# one_dollar_boad_rev4.net
KiCad netlist of a schematic drawn in EAGLE
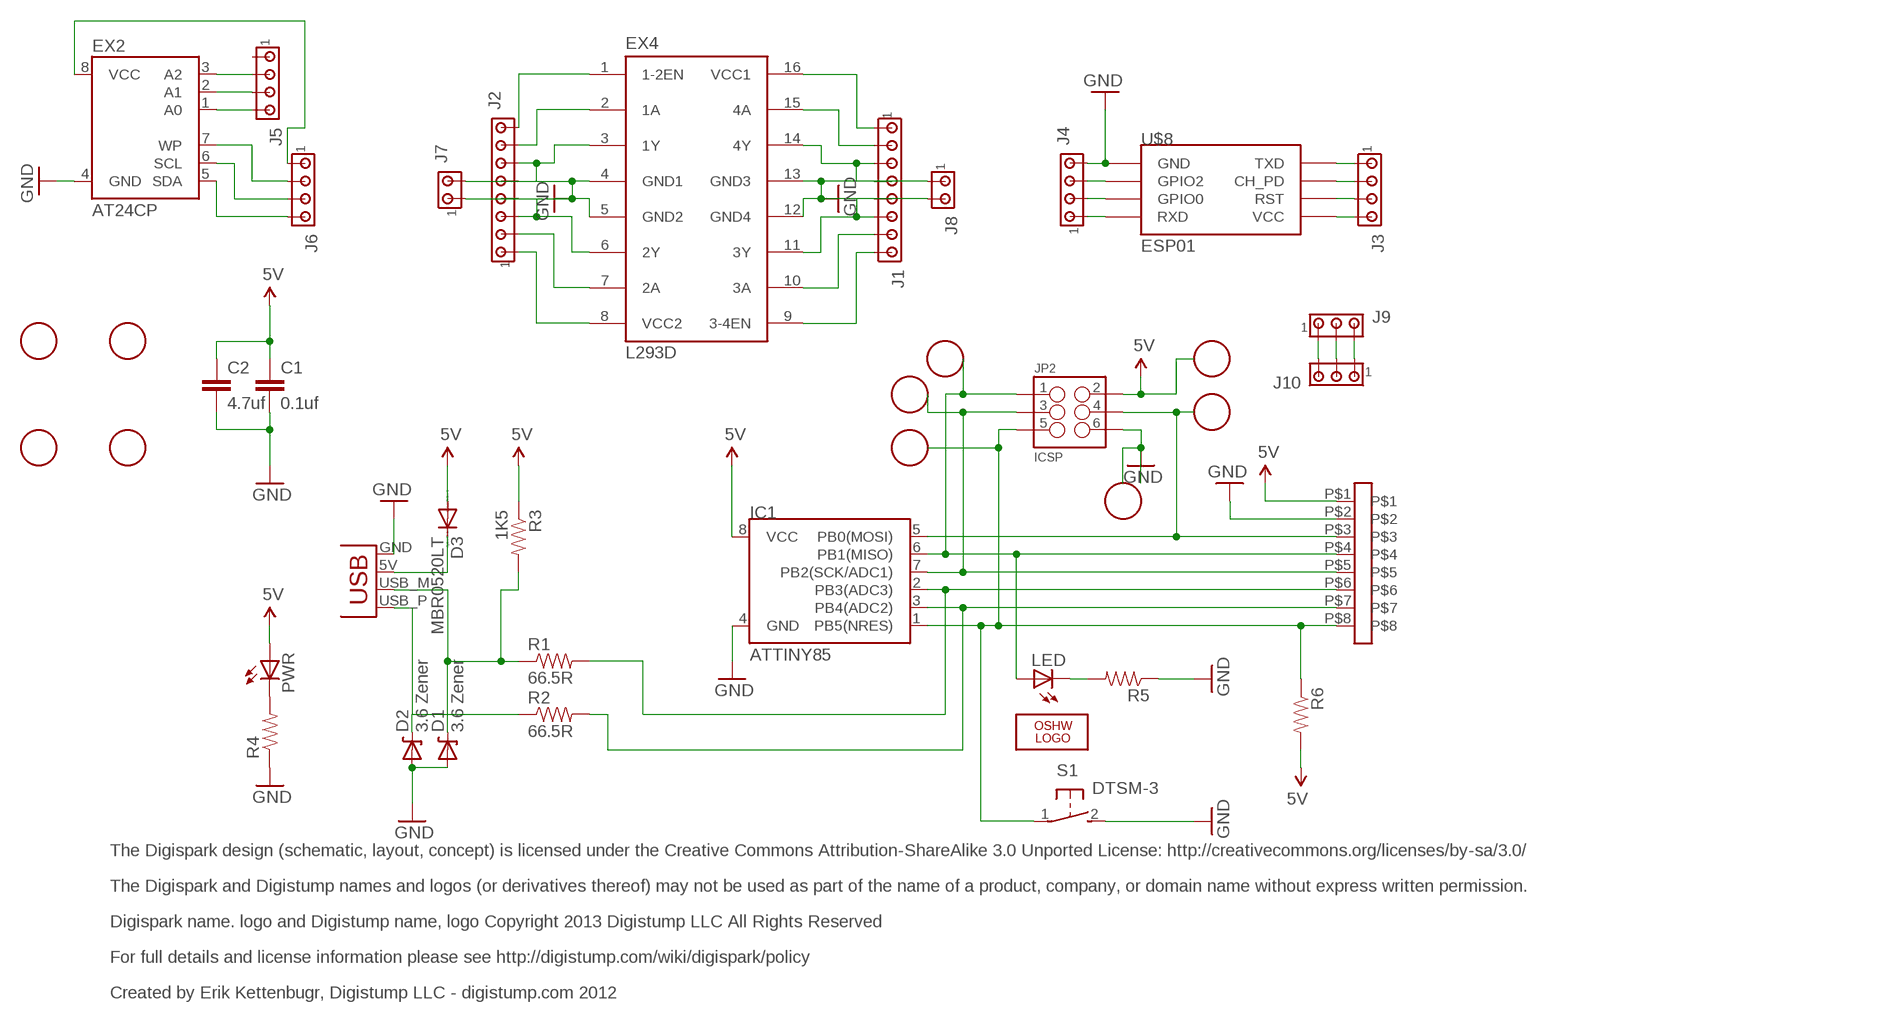
[diagram p0: schematic, sheet 1]

(export (version "E")
  (design (tool "Eeschema 10.0.6"))
  (components
    (comp (ref "C1")
      (value "0.1uf")
      (footprint "eagle-import:0402-CAP")
      (libsource (lib "eagle-import") (part "CAP0402-CAP"))
    )
    (comp (ref "C2")
      (value "4.7uf")
      (footprint "eagle-import:0805")
      (libsource (lib "eagle-import") (part "CAP0805"))
    )
    (comp (ref "CONNECTORBAR1")
      (value "FAMALEBAR01X08")
      (footprint "eagle-import:FEMEABARRA01X08")
      (libsource (lib "eagle-import") (part "FAMALEBAR01X08"))
    )
    (comp (ref "D1")
      (value "3.6 Zener")
      (footprint "eagle-import:SOD-323")
      (libsource (lib "eagle-import") (part "DIODE-ZENER-BZT52"))
    )
    (comp (ref "D2")
      (value "3.6 Zener")
      (footprint "eagle-import:SOD-323")
      (libsource (lib "eagle-import") (part "DIODE-ZENER-BZT52"))
    )
    (comp (ref "D3")
      (value "MBR0520LT")
      (footprint "eagle-import:SOD123")
      (libsource (lib "eagle-import") (part "MBR0520LT"))
    )
    (comp (ref "EX2")
      (value "AT24CP")
      (footprint "eagle-import:DIL08")
      (fields (field (name "MPN") "AT24C1024BW-SH-B"))
      (libsource (lib "eagle-import") (part "AT24CP"))
    )
    (comp (ref "EX4")
      (value "L293D")
      (footprint "eagle-import:DIL16")
      (libsource (lib "eagle-import") (part "L293D"))
    )
    (comp (ref "IC1")
      (value "ATTINY85")
      (footprint "eagle-import:SO08-EIAJ")
      (libsource (lib "eagle-import") (part "ATTINY45"))
    )
    (comp (ref "ICSP1")
      (value "ICSP")
      (footprint "eagle-import:ICSP")
      (libsource (lib "eagle-import") (part "ICSP"))
    )
    (comp (ref "ICSP2")
      (value "ICSP")
      (footprint "eagle-import:ICSP")
      (libsource (lib "eagle-import") (part "ICSP"))
    )
    (comp (ref "ICSP3")
      (value "ICSP")
      (footprint "eagle-import:ICSP")
      (libsource (lib "eagle-import") (part "ICSP"))
    )
    (comp (ref "ICSP4")
      (value "ICSP")
      (footprint "eagle-import:ICSP")
      (libsource (lib "eagle-import") (part "ICSP"))
    )
    (comp (ref "ICSP5")
      (value "ICSP")
      (footprint "eagle-import:ICSP")
      (libsource (lib "eagle-import") (part "ICSP"))
    )
    (comp (ref "ICSP6")
      (value "ICSP")
      (footprint "eagle-import:ICSP")
      (libsource (lib "eagle-import") (part "ICSP"))
    )
    (comp (ref "J1")
      (value "MTA08-100")
      (footprint "eagle-import:10X08MTA")
      (libsource (lib "eagle-import") (part "MTA08-100"))
    )
    (comp (ref "J2")
      (value "MTA08-100")
      (footprint "eagle-import:10X08MTA")
      (libsource (lib "eagle-import") (part "MTA08-100"))
    )
    (comp (ref "J3")
      (value "MTA04-100")
      (footprint "eagle-import:10X04MTA")
      (libsource (lib "eagle-import") (part "MTA04-100"))
    )
    (comp (ref "J4")
      (value "MTA04-100")
      (footprint "eagle-import:10X04MTA")
      (libsource (lib "eagle-import") (part "MTA04-100"))
    )
    (comp (ref "J5")
      (value "MTA04-100")
      (footprint "eagle-import:10X04MTA")
      (libsource (lib "eagle-import") (part "MTA04-100"))
    )
    (comp (ref "J6")
      (value "MTA04-100")
      (footprint "eagle-import:10X04MTA")
      (libsource (lib "eagle-import") (part "MTA04-100"))
    )
    (comp (ref "J7")
      (value "MTA02-100")
      (footprint "eagle-import:10X02MTA")
      (libsource (lib "eagle-import") (part "MTA02-100"))
    )
    (comp (ref "J8")
      (value "MTA02-100")
      (footprint "eagle-import:10X02MTA")
      (libsource (lib "eagle-import") (part "MTA02-100"))
    )
    (comp (ref "J9")
      (value "MTA03-100")
      (footprint "eagle-import:10X03MTA")
      (libsource (lib "eagle-import") (part "MTA03-100"))
    )
    (comp (ref "J10")
      (value "MTA03-100")
      (footprint "eagle-import:10X03MTA")
      (libsource (lib "eagle-import") (part "MTA03-100"))
    )
    (comp (ref "JP2")
      (value "ICSP")
      (footprint "eagle-import:2X3")
      (libsource (lib "eagle-import") (part "M03X22X3_SILK_MALE_PTH"))
    )
    (comp (ref "LED")
      (value "LED0603")
      (footprint "eagle-import:LED-0603")
      (libsource (lib "eagle-import") (part "LED0603"))
    )
    (comp (ref "LOGO2")
      (value "LOGO-OSHW-10MILX0200-NT")
      (footprint "eagle-import:OSHW_10X200_NOTEXT")
      (libsource (lib "eagle-import") (part "LOGO-OSHW-10MILX0200-NT"))
    )
    (comp (ref "PWR")
      (value "LED0603")
      (footprint "eagle-import:LED-0603")
      (libsource (lib "eagle-import") (part "LED0603"))
    )
    (comp (ref "R1")
      (value "66.5R")
      (footprint "eagle-import:0402-RES")
      (libsource (lib "eagle-import") (part "RESISTOR0402-RES"))
    )
    (comp (ref "R2")
      (value "66.5R")
      (footprint "eagle-import:0402-RES")
      (libsource (lib "eagle-import") (part "RESISTOR0402-RES"))
    )
    (comp (ref "R3")
      (value "1K5")
      (footprint "eagle-import:0402-RES")
      (libsource (lib "eagle-import") (part "RESISTOR0402-RES"))
    )
    (comp (ref "R4")
      (value "RESISTOR0402-RES")
      (footprint "eagle-import:0402-RES")
      (libsource (lib "eagle-import") (part "RESISTOR0402-RES"))
    )
    (comp (ref "R5")
      (value "RESISTOR0402-RES")
      (footprint "eagle-import:0402-RES")
      (libsource (lib "eagle-import") (part "RESISTOR0402-RES"))
    )
    (comp (ref "R6")
      (value "RESISTOR0402-RES")
      (footprint "eagle-import:0402-RES")
      (libsource (lib "eagle-import") (part "RESISTOR0402-RES"))
    )
    (comp (ref "S1")
      (value "DTSM-3")
      (footprint "eagle-import:DTSM-3")
      (libsource (lib "eagle-import") (part "DTSM-3"))
    )
    (comp (ref "U$8")
      (value "ESP01")
      (footprint "eagle-import:ESP01")
      (libsource (lib "eagle-import") (part "ESP01"))
    )
    (comp (ref "U$9")
      (value "ARDUINOPINAGEM")
      (footprint "eagle-import:ARDUINOPINAGEM")
      (libsource (lib "eagle-import") (part "ARDUINOPINAGEM"))
    )
    (comp (ref "X1")
      (value "USBPCB")
      (footprint "eagle-import:USB-A-PCB")
      (libsource (lib "eagle-import") (part "USBPCB"))
    )
  )
  (nets
    (net (code "1") (name "5V") (class "Default")
      (node (ref "C1") (pin "1") (pinfunction "1_1") (pintype "passive"))
      (node (ref "C2") (pin "1") (pinfunction "1_1") (pintype "passive"))
      (node (ref "CONNECTORBAR1") (pin "P$1") (pinfunction "P$1_P$1") (pintype "bidirectional"))
      (node (ref "D3") (pin "A") (pinfunction "A_A") (pintype "passive"))
      (node (ref "IC1") (pin "8") (pinfunction "VCC_8") (pintype "bidirectional"))
      (node (ref "JP2") (pin "2") (pinfunction "2_2") (pintype "bidirectional"))
      (node (ref "PWR") (pin "A") (pinfunction "A_A") (pintype "passive"))
      (node (ref "R3") (pin "1") (pinfunction "1_1") (pintype "passive"))
      (node (ref "R6") (pin "2") (pinfunction "2_2") (pintype "passive"))
    )
    (net (code "2") (name "GND") (class "Default")
      (node (ref "C1") (pin "2") (pinfunction "2_2") (pintype "passive"))
      (node (ref "C2") (pin "2") (pinfunction "2_2") (pintype "passive"))
      (node (ref "CONNECTORBAR1") (pin "P$2") (pinfunction "P$2_P$2") (pintype "bidirectional"))
      (node (ref "D1") (pin "2") (pinfunction "A_2") (pintype "passive"))
      (node (ref "D2") (pin "2") (pinfunction "A_2") (pintype "passive"))
      (node (ref "EX2") (pin "4") (pinfunction "GND_4") (pintype "power_in"))
      (node (ref "EX4") (pin "12") (pinfunction "GND4_12") (pintype "power_in"))
      (node (ref "EX4") (pin "13") (pinfunction "GND3_13") (pintype "power_in"))
      (node (ref "EX4") (pin "4") (pinfunction "GND1_4") (pintype "power_in"))
      (node (ref "EX4") (pin "5") (pinfunction "GND2_5") (pintype "power_in"))
      (node (ref "IC1") (pin "4") (pinfunction "GND_4") (pintype "bidirectional"))
      (node (ref "J1") (pin "4") (pinfunction "4_4") (pintype "passive"))
      (node (ref "J1") (pin "5") (pinfunction "5_5") (pintype "passive"))
      (node (ref "J2") (pin "4") (pinfunction "4_4") (pintype "passive"))
      (node (ref "J2") (pin "5") (pinfunction "5_5") (pintype "passive"))
      (node (ref "J4") (pin "4") (pinfunction "4_4") (pintype "passive"))
      (node (ref "JP2") (pin "6") (pinfunction "6_6") (pintype "bidirectional"))
      (node (ref "R4") (pin "1") (pinfunction "1_1") (pintype "passive"))
      (node (ref "R5") (pin "1") (pinfunction "1_1") (pintype "passive"))
      (node (ref "S1") (pin "2") (pinfunction "2_2") (pintype "passive"))
      (node (ref "U$8") (pin "GND") (pinfunction "GND_GND") (pintype "bidirectional"))
      (node (ref "X1") (pin "GND") (pinfunction "GND_GND") (pintype "bidirectional"))
    )
    (net (code "3") (name "Net-(D1-C)") (class "Default")
      (node (ref "D1") (pin "1") (pinfunction "C_1") (pintype "passive"))
      (node (ref "R1") (pin "1") (pinfunction "1_1") (pintype "passive"))
      (node (ref "R3") (pin "2") (pinfunction "2_2") (pintype "passive"))
      (node (ref "X1") (pin "USB_M") (pinfunction "D-_USB_M") (pintype "bidirectional"))
    )
    (net (code "4") (name "Net-(D2-C)") (class "Default")
      (node (ref "D2") (pin "1") (pinfunction "C_1") (pintype "passive"))
      (node (ref "R2") (pin "1") (pinfunction "1_1") (pintype "passive"))
      (node (ref "X1") (pin "USB_P") (pinfunction "D+_USB_P") (pintype "bidirectional"))
    )
    (net (code "5") (name "Net-(EX2-A0)") (class "Default")
      (node (ref "EX2") (pin "1") (pinfunction "A0_1") (pintype "input"))
      (node (ref "J5") (pin "4") (pinfunction "4_4") (pintype "passive"))
    )
    (net (code "6") (name "Net-(EX2-A1)") (class "Default")
      (node (ref "EX2") (pin "2") (pinfunction "A1_2") (pintype "input"))
      (node (ref "J5") (pin "3") (pinfunction "3_3") (pintype "passive"))
    )
    (net (code "7") (name "Net-(EX2-A2)") (class "Default")
      (node (ref "EX2") (pin "3") (pinfunction "A2_3") (pintype "input"))
      (node (ref "J5") (pin "2") (pinfunction "2_2") (pintype "passive"))
    )
    (net (code "8") (name "Net-(EX2-SCL)") (class "Default")
      (node (ref "EX2") (pin "6") (pinfunction "SCL_6") (pintype "bidirectional"))
      (node (ref "J6") (pin "3") (pinfunction "3_3") (pintype "passive"))
    )
    (net (code "9") (name "Net-(EX2-SDA)") (class "Default")
      (node (ref "EX2") (pin "5") (pinfunction "SDA_5") (pintype "bidirectional"))
      (node (ref "J6") (pin "4") (pinfunction "4_4") (pintype "passive"))
    )
    (net (code "10") (name "Net-(EX2-VCC)") (class "Default")
      (node (ref "EX2") (pin "8") (pinfunction "VCC_8") (pintype "power_in"))
      (node (ref "J6") (pin "1") (pinfunction "1_1") (pintype "passive"))
    )
    (net (code "11") (name "Net-(EX2-WP)") (class "Default")
      (node (ref "EX2") (pin "7") (pinfunction "WP_7") (pintype "input"))
      (node (ref "J6") (pin "2") (pinfunction "2_2") (pintype "passive"))
    )
    (net (code "12") (name "Net-(EX4-1-2EN)") (class "Default")
      (node (ref "EX4") (pin "1") (pinfunction "1-2EN_1") (pintype "input"))
      (node (ref "J2") (pin "8") (pinfunction "8_8") (pintype "passive"))
    )
    (net (code "13") (name "Net-(EX4-1A)") (class "Default")
      (node (ref "EX4") (pin "2") (pinfunction "1A_2") (pintype "input"))
      (node (ref "J2") (pin "7") (pinfunction "7_7") (pintype "passive"))
    )
    (net (code "14") (name "Net-(EX4-1Y)") (class "Default")
      (node (ref "EX4") (pin "3") (pinfunction "1Y_3") (pintype "output"))
      (node (ref "J2") (pin "6") (pinfunction "6_6") (pintype "passive"))
      (node (ref "J7") (pin "2") (pinfunction "2_2") (pintype "passive"))
    )
    (net (code "15") (name "Net-(EX4-2A)") (class "Default")
      (node (ref "EX4") (pin "7") (pinfunction "2A_7") (pintype "input"))
      (node (ref "J2") (pin "2") (pinfunction "2_2") (pintype "passive"))
    )
    (net (code "16") (name "Net-(EX4-2Y)") (class "Default")
      (node (ref "EX4") (pin "6") (pinfunction "2Y_6") (pintype "output"))
      (node (ref "J2") (pin "3") (pinfunction "3_3") (pintype "passive"))
      (node (ref "J7") (pin "1") (pinfunction "1_1") (pintype "passive"))
    )
    (net (code "17") (name "Net-(EX4-3-4EN)") (class "Default")
      (node (ref "EX4") (pin "9") (pinfunction "3-4EN_9") (pintype "input"))
      (node (ref "J1") (pin "8") (pinfunction "8_8") (pintype "passive"))
    )
    (net (code "18") (name "Net-(EX4-3A)") (class "Default")
      (node (ref "EX4") (pin "10") (pinfunction "3A_10") (pintype "input"))
      (node (ref "J1") (pin "7") (pinfunction "7_7") (pintype "passive"))
    )
    (net (code "19") (name "Net-(EX4-3Y)") (class "Default")
      (node (ref "EX4") (pin "11") (pinfunction "3Y_11") (pintype "output"))
      (node (ref "J1") (pin "6") (pinfunction "6_6") (pintype "passive"))
      (node (ref "J8") (pin "2") (pinfunction "2_2") (pintype "passive"))
    )
    (net (code "20") (name "Net-(EX4-4A)") (class "Default")
      (node (ref "EX4") (pin "15") (pinfunction "4A_15") (pintype "input"))
      (node (ref "J1") (pin "2") (pinfunction "2_2") (pintype "passive"))
    )
    (net (code "21") (name "Net-(EX4-4Y)") (class "Default")
      (node (ref "EX4") (pin "14") (pinfunction "4Y_14") (pintype "output"))
      (node (ref "J1") (pin "3") (pinfunction "3_3") (pintype "passive"))
      (node (ref "J8") (pin "1") (pinfunction "1_1") (pintype "passive"))
    )
    (net (code "22") (name "Net-(EX4-VCC1)") (class "Default")
      (node (ref "EX4") (pin "16") (pinfunction "VCC1_16") (pintype "power_in"))
      (node (ref "J1") (pin "1") (pinfunction "1_1") (pintype "passive"))
    )
    (net (code "23") (name "Net-(EX4-VCC2)") (class "Default")
      (node (ref "EX4") (pin "8") (pinfunction "VCC2_8") (pintype "power_in"))
      (node (ref "J2") (pin "1") (pinfunction "1_1") (pintype "passive"))
    )
    (net (code "24") (name "Net-(IC1-PB0(MOSI))") (class "Default")
      (node (ref "CONNECTORBAR1") (pin "P$3") (pinfunction "P$3_P$3") (pintype "bidirectional"))
      (node (ref "IC1") (pin "5") (pinfunction "PB0(MOSI)_5") (pintype "bidirectional"))
      (node (ref "JP2") (pin "4") (pinfunction "4_4") (pintype "bidirectional"))
    )
    (net (code "25") (name "Net-(IC1-PB1(MISO))") (class "Default")
      (node (ref "CONNECTORBAR1") (pin "P$4") (pinfunction "P$4_P$4") (pintype "bidirectional"))
      (node (ref "IC1") (pin "6") (pinfunction "PB1(MISO)_6") (pintype "bidirectional"))
      (node (ref "JP2") (pin "1") (pinfunction "1_1") (pintype "bidirectional"))
      (node (ref "LED") (pin "A") (pinfunction "A_A") (pintype "passive"))
    )
    (net (code "26") (name "Net-(IC1-PB2(SCK{slash}ADC1))") (class "Default")
      (node (ref "CONNECTORBAR1") (pin "P$5") (pinfunction "P$5_P$5") (pintype "bidirectional"))
      (node (ref "IC1") (pin "7") (pinfunction "PB2(SCK/ADC1)_7") (pintype "bidirectional"))
      (node (ref "JP2") (pin "3") (pinfunction "3_3") (pintype "bidirectional"))
    )
    (net (code "27") (name "Net-(IC1-PB3(ADC3))") (class "Default")
      (node (ref "CONNECTORBAR1") (pin "P$6") (pinfunction "P$6_P$6") (pintype "bidirectional"))
      (node (ref "IC1") (pin "2") (pinfunction "PB3(ADC3)_2") (pintype "bidirectional"))
      (node (ref "R1") (pin "2") (pinfunction "2_2") (pintype "passive"))
    )
    (net (code "28") (name "Net-(IC1-PB4(ADC2))") (class "Default")
      (node (ref "CONNECTORBAR1") (pin "P$7") (pinfunction "P$7_P$7") (pintype "bidirectional"))
      (node (ref "IC1") (pin "3") (pinfunction "PB4(ADC2)_3") (pintype "bidirectional"))
      (node (ref "R2") (pin "2") (pinfunction "2_2") (pintype "passive"))
    )
    (net (code "29") (name "Net-(IC1-PB5(NRES))") (class "Default")
      (node (ref "CONNECTORBAR1") (pin "P$8") (pinfunction "P$8_P$8") (pintype "bidirectional"))
      (node (ref "IC1") (pin "1") (pinfunction "PB5(NRES)_1") (pintype "bidirectional"))
      (node (ref "JP2") (pin "5") (pinfunction "5_5") (pintype "bidirectional"))
      (node (ref "R6") (pin "1") (pinfunction "1_1") (pintype "passive"))
      (node (ref "S1") (pin "1") (pinfunction "1_1") (pintype "passive"))
    )
    (net (code "30") (name "Net-(J3-Pad2)") (class "Default")
      (node (ref "J3") (pin "2") (pinfunction "2_2") (pintype "passive"))
      (node (ref "U$8") (pin "CH_PD") (pinfunction "CH_PD_CH_PD") (pintype "bidirectional"))
    )
    (net (code "31") (name "Net-(J3-Pad3)") (class "Default")
      (node (ref "J3") (pin "3") (pinfunction "3_3") (pintype "passive"))
      (node (ref "U$8") (pin "RST") (pinfunction "RST_RST") (pintype "bidirectional"))
    )
    (net (code "32") (name "Net-(J3-Pad4)") (class "Default")
      (node (ref "J3") (pin "4") (pinfunction "4_4") (pintype "passive"))
      (node (ref "U$8") (pin "VCC") (pinfunction "VCC_VCC") (pintype "bidirectional"))
    )
    (net (code "33") (name "Net-(J4-Pad2)") (class "Default")
      (node (ref "J4") (pin "2") (pinfunction "2_2") (pintype "passive"))
      (node (ref "U$8") (pin "GPIO0") (pinfunction "GPIO0_GPIO0") (pintype "bidirectional"))
    )
    (net (code "34") (name "Net-(J4-Pad3)") (class "Default")
      (node (ref "J4") (pin "3") (pinfunction "3_3") (pintype "passive"))
      (node (ref "U$8") (pin "GPIO2") (pinfunction "GPIO2_GPIO2") (pintype "bidirectional"))
    )
    (net (code "35") (name "Net-(J10-Pad1)") (class "Default")
      (node (ref "J10") (pin "1") (pinfunction "1_1") (pintype "passive"))
      (node (ref "J9") (pin "3") (pinfunction "3_3") (pintype "passive"))
    )
    (net (code "36") (name "Net-(J10-Pad2)") (class "Default")
      (node (ref "J10") (pin "2") (pinfunction "2_2") (pintype "passive"))
      (node (ref "J9") (pin "2") (pinfunction "2_2") (pintype "passive"))
    )
    (net (code "37") (name "Net-(J10-Pad3)") (class "Default")
      (node (ref "J10") (pin "3") (pinfunction "3_3") (pintype "passive"))
      (node (ref "J9") (pin "1") (pinfunction "1_1") (pintype "passive"))
    )
    (net (code "38") (name "Net-(LED-PadC)") (class "Default")
      (node (ref "LED") (pin "C") (pinfunction "C_C") (pintype "passive"))
      (node (ref "R5") (pin "2") (pinfunction "2_2") (pintype "passive"))
    )
    (net (code "39") (name "Net-(PWR-PadC)") (class "Default")
      (node (ref "PWR") (pin "C") (pinfunction "C_C") (pintype "passive"))
      (node (ref "R4") (pin "2") (pinfunction "2_2") (pintype "passive"))
    )
    (net (code "40") (name "Net-(U$8-RXD)") (class "Default")
      (node (ref "J4") (pin "1") (pinfunction "1_1") (pintype "passive"))
      (node (ref "U$8") (pin "RX") (pinfunction "RXD_RX") (pintype "bidirectional"))
    )
    (net (code "41") (name "Net-(U$8-TXD)") (class "Default")
      (node (ref "J3") (pin "1") (pinfunction "1_1") (pintype "passive"))
      (node (ref "U$8") (pin "TX") (pinfunction "TXD_TX") (pintype "bidirectional"))
    )
    (net (code "42") (name "Net-(X1-VBUS)") (class "Default")
      (node (ref "D3") (pin "C") (pinfunction "C_C") (pintype "passive"))
      (node (ref "X1") (pin "5V") (pinfunction "VBUS_5V") (pintype "bidirectional"))
    )
    (net (code "43") (name "unconnected-(J5-Pad1)") (class "Default")
      (node (ref "J5") (pin "1") (pinfunction "1_1") (pintype "passive"))
    )
  )
)
